# opg_receiver_schematics.net
KiCad netlist of a schematic drawn in Altium Designer
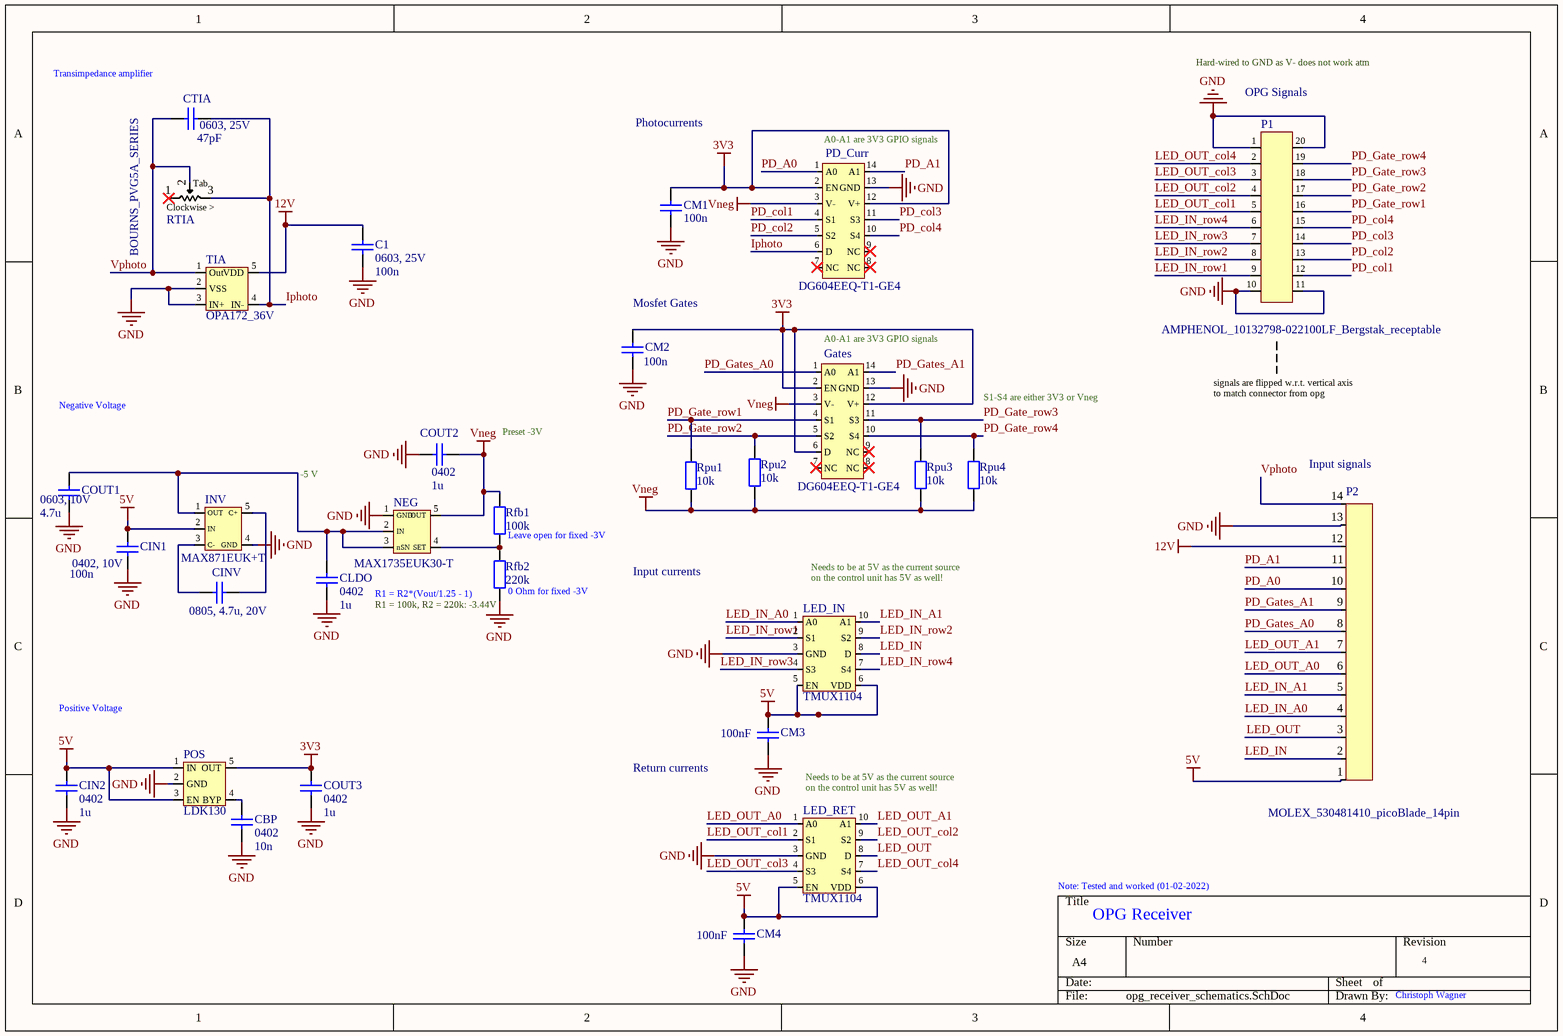
[diagram p0: opg_receiver_schematics.SchDoc]

(export (version "E")
  (design (tool "Eeschema 10.0.6"))
  (components
    (comp (ref "C1")
      (value "0603, 25V")
      (footprint "1608[0603]")
      (description "Capacitor (Semiconductor SIM Model)")
      (fields (field (name "ALTIUM_VALUE") "100n") (field (name "PUBLISHER") "Altium Limited"))
      (libsource (lib "Miscellaneous Devices") (part "Cap Semi"))
    )
    (comp (ref "CBP")
      (value "0402")
      (footprint "0402")
      (description "Capacitor (Semiconductor SIM Model)")
      (fields (field (name "ALTIUM_VALUE") "10n") (field (name "PUBLISHER") "Altium Limited"))
      (libsource (lib "Miscellaneous Devices") (part "Cap Semi"))
    )
    (comp (ref "CIN1")
      (value "0402, 10V")
      (footprint "1608[0603]")
      (description "Capacitor (Semiconductor SIM Model)")
      (fields (field (name "ALTIUM_VALUE") "100n") (field (name "PUBLISHER") "Altium Limited"))
      (libsource (lib "Miscellaneous Devices") (part "Cap Semi"))
    )
    (comp (ref "CIN2")
      (value "0402")
      (footprint "0402")
      (description "Capacitor (Semiconductor SIM Model)")
      (fields (field (name "ALTIUM_VALUE") "1u") (field (name "PUBLISHER") "Altium Limited"))
      (libsource (lib "Miscellaneous Devices") (part "Cap Semi"))
    )
    (comp (ref "CINV")
      (value "0805, 4.7u, 20V")
      (footprint "WCAP-CSGP_0805_H=0.8mm_Reflow")
      (description "WCAP-CSGP Multilayer Ceramic Chip Capacitor, General Purpose, size 0805, X7R, 680pF, 16V")
      (fields
        (field (name "MANUFACTURER PART NUMBER") "885012207032")
        (field (name "MANUFACTURER") "Wurth Elektronik")
      )
      (libsource (lib "capacitor_0805") (part "885012207032"))
    )
    (comp (ref "CLDO")
      (value "0402")
      (footprint "0402")
      (description "Capacitor (Semiconductor SIM Model)")
      (fields (field (name "ALTIUM_VALUE") "1u") (field (name "PUBLISHER") "Altium Limited"))
      (libsource (lib "Miscellaneous Devices") (part "Cap Semi"))
    )
    (comp (ref "CM1")
      (value "100n")
      (footprint "0402")
      (description "Capacitor (Semiconductor SIM Model)")
      (fields (field (name "PUBLISHER") "Altium Limited"))
      (libsource (lib "Miscellaneous Devices") (part "Cap Semi"))
    )
    (comp (ref "CM2")
      (value "100n")
      (footprint "0402")
      (description "Capacitor (Semiconductor SIM Model)")
      (fields (field (name "PUBLISHER") "Altium Limited"))
      (libsource (lib "Miscellaneous Devices") (part "Cap Semi"))
    )
    (comp (ref "CM3")
      (value "100nF")
      (footprint "0402")
      (description "Capacitor (Semiconductor SIM Model)")
      (fields (field (name "PUBLISHER") "Altium Limited"))
      (libsource (lib "Miscellaneous Devices") (part "Cap Semi"))
    )
    (comp (ref "CM4")
      (value "100nF")
      (footprint "0402")
      (description "Capacitor (Semiconductor SIM Model)")
      (fields (field (name "PUBLISHER") "Altium Limited"))
      (libsource (lib "Miscellaneous Devices") (part "Cap Semi"))
    )
    (comp (ref "COUT1")
      (value "0603, 10V")
      (footprint "1608[0603]")
      (description "Capacitor (Semiconductor SIM Model)")
      (fields (field (name "ALTIUM_VALUE") "4.7u") (field (name "PUBLISHER") "Altium Limited"))
      (libsource (lib "Miscellaneous Devices") (part "Cap Semi"))
    )
    (comp (ref "COUT2")
      (value "0402")
      (footprint "0402")
      (description "Capacitor (Semiconductor SIM Model)")
      (fields (field (name "ALTIUM_VALUE") "1u") (field (name "PUBLISHER") "Altium Limited"))
      (libsource (lib "Miscellaneous Devices") (part "Cap Semi"))
    )
    (comp (ref "COUT3")
      (value "0402")
      (footprint "0402")
      (description "Capacitor (Semiconductor SIM Model)")
      (fields (field (name "ALTIUM_VALUE") "1u") (field (name "PUBLISHER") "Altium Limited"))
      (libsource (lib "Miscellaneous Devices") (part "Cap Semi"))
    )
    (comp (ref "CTIA")
      (value "0603, 25V")
      (footprint "1608[0603]")
      (description "Capacitor (Semiconductor SIM Model)")
      (fields (field (name "ALTIUM_VALUE") "47pF") (field (name "PUBLISHER") "Altium Limited"))
      (libsource (lib "Miscellaneous Devices") (part "Cap Semi"))
    )
    (comp (ref "Gates")
      (value "DG604EEQ-T1-GE4")
      (footprint "DG604EEQ-T1-GE4")
      (description "Multiplex-Schalter IC CMOS 4:1 Multiplxr 14-pin TSSOP")
      (libsource (lib "Multiplexer") (part "DG604EEQ-T1-GE4"))
    )
    (comp (ref "INV")
      (value "MAX871EUK+T")
      (footprint "MAX871EUK+T")
      (description "500 kHz Switched-Capacitor Voltage Inverters")
      (libsource (lib "Regulator") (part "MAX871EUK+T"))
    )
    (comp (ref "LED_IN")
      (value "TMUX1104")
      (footprint "TMUX1104_legged")
      (description "4:1 MUX")
      (libsource (lib "Multiplexer") (part "TMUX1104"))
    )
    (comp (ref "LED_RET")
      (value "TMUX1104")
      (footprint "TMUX1104_legged")
      (description "4:1 MUX")
      (libsource (lib "Multiplexer") (part "TMUX1104"))
    )
    (comp (ref "NEG")
      (value "MAX1735EUK30-T")
      (footprint "MAX1735EUKxx-T")
      (libsource (lib "Regulator") (part "MAX1735EUKxx-T"))
    )
    (comp (ref "P1")
      (value "AMPHENOL_10132798-022100LF_Bergstak_receptable")
      (footprint "AMPHENOL_10132798-022100LF_Bergstak_receptable")
      (description "20 pin, 0.5 mm pitch, 3 mm mated height, female/receptable")
      (libsource (lib "Connectors") (part "AMPHENOL_10132798-022100LF_Bergstak_receptable"))
    )
    (comp (ref "P2")
      (value "MOLEX_530481410_picoBlade_14pin")
      (footprint "MOLEX_530481410_picoBlade_14pin")
      (libsource (lib "Connectors") (part "MOLEX_530481410_picoBlade_14pin"))
    )
    (comp (ref "PD_Curr")
      (value "DG604EEQ-T1-GE4")
      (footprint "DG604EEQ-T1-GE4")
      (description "Multiplex-Schalter IC CMOS 4:1 Multiplxr 14-pin TSSOP")
      (libsource (lib "Multiplexer") (part "DG604EEQ-T1-GE4"))
    )
    (comp (ref "POS")
      (value "LDK130")
      (footprint "LDK130")
      (description "300 mA low quiescent current very low noise LDO")
      (libsource (lib "Regulator") (part "LDK130"))
    )
    (comp (ref "Rfb1")
      (value "100k")
      (footprint "WRIS-KSKE_0805")
      (description "WRIS-KSKE SMT Thick Film Resistor, size 0805, 1Ohm, 0.33W")
      (fields
        (field (name "MANUFACTURER") "Wurth Elektronik")
        (field (name "MANUFACTURER PART NUMBER") "560050320011")
      )
      (libsource (lib "Wurth_thick_film_resistors") (part "560050320011"))
    )
    (comp (ref "Rfb2")
      (value "220k")
      (footprint "WRIS-KSKE_0805")
      (description "WRIS-KSKE SMT Thick Film Resistor, size 0805, 1Ohm, 0.33W")
      (fields
        (field (name "MANUFACTURER") "Wurth Elektronik")
        (field (name "MANUFACTURER PART NUMBER") "560050320011")
      )
      (libsource (lib "Wurth_thick_film_resistors") (part "560050320011"))
    )
    (comp (ref "Rpu1")
      (value "10k")
      (footprint "WRIS-KSKE_0402")
      (description "WRIS-KSKE SMT Thick Film Resistor, size 0402, 10Ohm, 0.125W")
      (fields
        (field (name "MANUFACTURER") "Wurth Elektronik")
        (field (name "MANUFACTURER PART NUMBER") "560050310009")
      )
      (libsource (lib "Wurth_thick_film_resistors") (part "560050310009"))
    )
    (comp (ref "Rpu2")
      (value "10k")
      (footprint "WRIS-KSKE_0402")
      (description "WRIS-KSKE SMT Thick Film Resistor, size 0402, 10Ohm, 0.125W")
      (fields
        (field (name "MANUFACTURER") "Wurth Elektronik")
        (field (name "MANUFACTURER PART NUMBER") "560050310009")
      )
      (libsource (lib "Wurth_thick_film_resistors") (part "560050310009"))
    )
    (comp (ref "Rpu3")
      (value "10k")
      (footprint "WRIS-KSKE_0402")
      (description "WRIS-KSKE SMT Thick Film Resistor, size 0402, 10Ohm, 0.125W")
      (fields
        (field (name "MANUFACTURER") "Wurth Elektronik")
        (field (name "MANUFACTURER PART NUMBER") "560050310009")
      )
      (libsource (lib "Wurth_thick_film_resistors") (part "560050310009"))
    )
    (comp (ref "Rpu4")
      (value "10k")
      (footprint "WRIS-KSKE_0402")
      (description "WRIS-KSKE SMT Thick Film Resistor, size 0402, 10Ohm, 0.125W")
      (fields
        (field (name "MANUFACTURER") "Wurth Elektronik")
        (field (name "MANUFACTURER PART NUMBER") "560050310009")
      )
      (libsource (lib "Wurth_thick_film_resistors") (part "560050310009"))
    )
    (comp (ref "RTIA")
      (value "BOURNS_PVG5A_SERIES")
      (footprint "BOURNS_PVG5A_SERIES")
      (libsource (lib "Potentiometer") (part "BOURNS_PVG5A_SERIES"))
    )
    (comp (ref "TIA")
      (value "OPA172_36V")
      (footprint "OPA172_36V_SC70-5")
      (description "OPAx172 36-V, Single-Supply, 10-MHz, Rail-to-Rail Output Operational Amplifiers")
      (libsource (lib "OP_Amps") (part "OPA172_36V"))
    )
  )
  (nets
    (net (code "1") (name "/Iphoto") (class "Default")
      (node (ref "CTIA") (pin "1") (pinfunction "1_1") (pintype "passive"))
      (node (ref "PD_Curr") (pin "6") (pinfunction "D_6") (pintype "passive"))
      (node (ref "RTIA") (pin "3") (pintype "passive"))
      (node (ref "TIA") (pin "4") (pinfunction "IN-_4") (pintype "passive"))
    )
    (net (code "2") (name "/LED_IN") (class "Default")
      (node (ref "LED_IN") (pin "8") (pinfunction "D_8") (pintype "passive"))
      (node (ref "P2") (pin "2") (pintype "passive"))
    )
    (net (code "3") (name "/LED_IN_A0") (class "Default")
      (node (ref "LED_IN") (pin "1") (pinfunction "A0_1") (pintype "passive"))
      (node (ref "P2") (pin "4") (pintype "passive"))
    )
    (net (code "4") (name "/LED_IN_A1") (class "Default")
      (node (ref "LED_IN") (pin "10") (pinfunction "A1_10") (pintype "passive"))
      (node (ref "P2") (pin "5") (pintype "passive"))
    )
    (net (code "5") (name "/LED_IN_row1") (class "Default")
      (node (ref "LED_IN") (pin "2") (pinfunction "S1_2") (pintype "passive"))
      (node (ref "P1") (pin "9") (pintype "passive"))
    )
    (net (code "6") (name "/LED_IN_row2") (class "Default")
      (node (ref "LED_IN") (pin "9") (pinfunction "S2_9") (pintype "passive"))
      (node (ref "P1") (pin "8") (pintype "passive"))
    )
    (net (code "7") (name "/LED_IN_row3") (class "Default")
      (node (ref "LED_IN") (pin "4") (pinfunction "S3_4") (pintype "passive"))
      (node (ref "P1") (pin "7") (pintype "passive"))
    )
    (net (code "8") (name "/LED_IN_row4") (class "Default")
      (node (ref "LED_IN") (pin "7") (pinfunction "S4_7") (pintype "passive"))
      (node (ref "P1") (pin "6") (pintype "passive"))
    )
    (net (code "9") (name "/LED_OUT") (class "Default")
      (node (ref "LED_RET") (pin "8") (pinfunction "D_8") (pintype "passive"))
      (node (ref "P2") (pin "3") (pintype "passive"))
    )
    (net (code "10") (name "/LED_OUT_A0") (class "Default")
      (node (ref "LED_RET") (pin "1") (pinfunction "A0_1") (pintype "passive"))
      (node (ref "P2") (pin "6") (pintype "passive"))
    )
    (net (code "11") (name "/LED_OUT_A1") (class "Default")
      (node (ref "LED_RET") (pin "10") (pinfunction "A1_10") (pintype "passive"))
      (node (ref "P2") (pin "7") (pintype "passive"))
    )
    (net (code "12") (name "/LED_OUT_col1") (class "Default")
      (node (ref "LED_RET") (pin "2") (pinfunction "S1_2") (pintype "passive"))
      (node (ref "P1") (pin "5") (pintype "passive"))
    )
    (net (code "13") (name "/LED_OUT_col2") (class "Default")
      (node (ref "LED_RET") (pin "9") (pinfunction "S2_9") (pintype "passive"))
      (node (ref "P1") (pin "4") (pintype "passive"))
    )
    (net (code "14") (name "/LED_OUT_col3") (class "Default")
      (node (ref "LED_RET") (pin "4") (pinfunction "S3_4") (pintype "passive"))
      (node (ref "P1") (pin "3") (pintype "passive"))
    )
    (net (code "15") (name "/LED_OUT_col4") (class "Default")
      (node (ref "LED_RET") (pin "7") (pinfunction "S4_7") (pintype "passive"))
      (node (ref "P1") (pin "2") (pintype "passive"))
    )
    (net (code "16") (name "/PD_A0") (class "Default")
      (node (ref "P2") (pin "10") (pintype "passive"))
      (node (ref "PD_Curr") (pin "1") (pinfunction "A0_1") (pintype "passive"))
    )
    (net (code "17") (name "/PD_A1") (class "Default")
      (node (ref "P2") (pin "11") (pintype "passive"))
      (node (ref "PD_Curr") (pin "14") (pinfunction "A1_14") (pintype "passive"))
    )
    (net (code "18") (name "/PD_Gate_row1") (class "Default")
      (node (ref "Gates") (pin "4") (pinfunction "S1_4") (pintype "passive"))
      (node (ref "P1") (pin "16") (pintype "passive"))
      (node (ref "Rpu1") (pin "2") (pinfunction "2_2") (pintype "passive"))
    )
    (net (code "19") (name "/PD_Gate_row2") (class "Default")
      (node (ref "Gates") (pin "5") (pinfunction "S2_5") (pintype "passive"))
      (node (ref "P1") (pin "17") (pintype "passive"))
      (node (ref "Rpu2") (pin "2") (pinfunction "2_2") (pintype "passive"))
    )
    (net (code "20") (name "/PD_Gate_row3") (class "Default")
      (node (ref "Gates") (pin "11") (pinfunction "S3_11") (pintype "passive"))
      (node (ref "P1") (pin "18") (pintype "passive"))
      (node (ref "Rpu3") (pin "2") (pinfunction "2_2") (pintype "passive"))
    )
    (net (code "21") (name "/PD_Gate_row4") (class "Default")
      (node (ref "Gates") (pin "10") (pinfunction "S4_10") (pintype "passive"))
      (node (ref "P1") (pin "19") (pintype "passive"))
      (node (ref "Rpu4") (pin "2") (pinfunction "2_2") (pintype "passive"))
    )
    (net (code "22") (name "/PD_Gates_A0") (class "Default")
      (node (ref "Gates") (pin "1") (pinfunction "A0_1") (pintype "passive"))
      (node (ref "P2") (pin "8") (pintype "passive"))
    )
    (net (code "23") (name "/PD_Gates_A1") (class "Default")
      (node (ref "Gates") (pin "14") (pinfunction "A1_14") (pintype "passive"))
      (node (ref "P2") (pin "9") (pintype "passive"))
    )
    (net (code "24") (name "/PD_col1") (class "Default")
      (node (ref "P1") (pin "12") (pintype "passive"))
      (node (ref "PD_Curr") (pin "4") (pinfunction "S1_4") (pintype "passive"))
    )
    (net (code "25") (name "/PD_col2") (class "Default")
      (node (ref "P1") (pin "13") (pintype "passive"))
      (node (ref "PD_Curr") (pin "5") (pinfunction "S2_5") (pintype "passive"))
    )
    (net (code "26") (name "/PD_col3") (class "Default")
      (node (ref "P1") (pin "14") (pintype "passive"))
      (node (ref "PD_Curr") (pin "11") (pinfunction "S3_11") (pintype "passive"))
    )
    (net (code "27") (name "/PD_col4") (class "Default")
      (node (ref "P1") (pin "15") (pintype "passive"))
      (node (ref "PD_Curr") (pin "10") (pinfunction "S4_10") (pintype "passive"))
    )
    (net (code "28") (name "/Vphoto") (class "Default")
      (node (ref "CTIA") (pin "2") (pinfunction "2_2") (pintype "passive"))
      (node (ref "P2") (pin "14") (pintype "passive"))
      (node (ref "RTIA") (pin "2") (pintype "passive"))
      (node (ref "TIA") (pin "1") (pinfunction "Out_1") (pintype "passive"))
    )
    (net (code "29") (name "3V3") (class "Default")
      (node (ref "CM1") (pin "2") (pinfunction "2_2") (pintype "passive"))
      (node (ref "CM2") (pin "2") (pinfunction "2_2") (pintype "passive"))
      (node (ref "COUT3") (pin "2") (pinfunction "2_2") (pintype "passive"))
      (node (ref "Gates") (pin "12") (pinfunction "V+_12") (pintype "passive"))
      (node (ref "Gates") (pin "2") (pinfunction "EN_2") (pintype "passive"))
      (node (ref "Gates") (pin "6") (pinfunction "D_6") (pintype "passive"))
      (node (ref "PD_Curr") (pin "12") (pinfunction "V+_12") (pintype "passive"))
      (node (ref "PD_Curr") (pin "2") (pinfunction "EN_2") (pintype "passive"))
      (node (ref "POS") (pin "5") (pinfunction "OUT_5") (pintype "passive"))
    )
    (net (code "30") (name "5V") (class "Default")
      (node (ref "CIN1") (pin "2") (pinfunction "2_2") (pintype "passive"))
      (node (ref "CIN2") (pin "1") (pinfunction "1_1") (pintype "passive"))
      (node (ref "CM3") (pin "1") (pinfunction "1_1") (pintype "passive"))
      (node (ref "CM4") (pin "2") (pinfunction "2_2") (pintype "passive"))
      (node (ref "INV") (pin "2") (pinfunction "IN_2") (pintype "passive"))
      (node (ref "LED_IN") (pin "5") (pinfunction "EN_5") (pintype "passive"))
      (node (ref "LED_IN") (pin "6") (pinfunction "VDD_6") (pintype "passive"))
      (node (ref "LED_RET") (pin "5") (pinfunction "EN_5") (pintype "passive"))
      (node (ref "LED_RET") (pin "6") (pinfunction "VDD_6") (pintype "passive"))
      (node (ref "P2") (pin "1") (pintype "passive"))
      (node (ref "POS") (pin "1") (pinfunction "IN_1") (pintype "passive"))
      (node (ref "POS") (pin "3") (pinfunction "EN_3") (pintype "passive"))
    )
    (net (code "31") (name "12V") (class "Default")
      (node (ref "C1") (pin "2") (pinfunction "2_2") (pintype "passive"))
      (node (ref "P2") (pin "12") (pintype "passive"))
      (node (ref "TIA") (pin "5") (pinfunction "VDD_5") (pintype "passive"))
    )
    (net (code "32") (name "GND") (class "Default")
      (node (ref "C1") (pin "1") (pinfunction "1_1") (pintype "passive"))
      (node (ref "CBP") (pin "2") (pinfunction "2_2") (pintype "passive"))
      (node (ref "CIN1") (pin "1") (pinfunction "1_1") (pintype "passive"))
      (node (ref "CIN2") (pin "2") (pinfunction "2_2") (pintype "passive"))
      (node (ref "CLDO") (pin "2") (pinfunction "2_2") (pintype "passive"))
      (node (ref "CM1") (pin "1") (pinfunction "1_1") (pintype "passive"))
      (node (ref "CM2") (pin "1") (pinfunction "1_1") (pintype "passive"))
      (node (ref "CM3") (pin "2") (pinfunction "2_2") (pintype "passive"))
      (node (ref "CM4") (pin "1") (pinfunction "1_1") (pintype "passive"))
      (node (ref "COUT1") (pin "2") (pinfunction "2_2") (pintype "passive"))
      (node (ref "COUT2") (pin "1") (pinfunction "1_1") (pintype "passive"))
      (node (ref "COUT3") (pin "1") (pinfunction "1_1") (pintype "passive"))
      (node (ref "Gates") (pin "13") (pinfunction "GND_13") (pintype "passive"))
      (node (ref "INV") (pin "4") (pinfunction "GND_4") (pintype "passive"))
      (node (ref "LED_IN") (pin "3") (pinfunction "GND_3") (pintype "passive"))
      (node (ref "LED_RET") (pin "3") (pinfunction "GND_3") (pintype "passive"))
      (node (ref "NEG") (pin "1") (pinfunction "GND_1") (pintype "passive"))
      (node (ref "P1") (pin "1") (pintype "passive"))
      (node (ref "P1") (pin "10") (pintype "passive"))
      (node (ref "P1") (pin "11") (pintype "passive"))
      (node (ref "P1") (pin "20") (pintype "passive"))
      (node (ref "P2") (pin "13") (pintype "passive"))
      (node (ref "PD_Curr") (pin "13") (pinfunction "GND_13") (pintype "passive"))
      (node (ref "POS") (pin "2") (pinfunction "GND_2") (pintype "passive"))
      (node (ref "Rfb2") (pin "2") (pinfunction "2_2") (pintype "passive"))
      (node (ref "TIA") (pin "2") (pinfunction "VSS_2") (pintype "passive"))
      (node (ref "TIA") (pin "3") (pinfunction "IN+_3") (pintype "passive"))
    )
    (net (code "33") (name "Net-(INV-C+)") (class "Default")
      (node (ref "CINV") (pin "2") (pinfunction "2_2") (pintype "passive"))
      (node (ref "INV") (pin "5") (pinfunction "C+_5") (pintype "passive"))
    )
    (net (code "34") (name "Net-(INV-C-)") (class "Default")
      (node (ref "CINV") (pin "1") (pinfunction "1_1") (pintype "passive"))
      (node (ref "INV") (pin "3") (pinfunction "C-_3") (pintype "passive"))
    )
    (net (code "35") (name "Net-(INV-OUT)") (class "Default")
      (node (ref "CLDO") (pin "1") (pinfunction "1_1") (pintype "passive"))
      (node (ref "COUT1") (pin "1") (pinfunction "1_1") (pintype "passive"))
      (node (ref "INV") (pin "1") (pinfunction "OUT_1") (pintype "passive"))
      (node (ref "NEG") (pin "2") (pinfunction "IN_2") (pintype "passive"))
      (node (ref "NEG") (pin "3") (pinfunction "nSN_3") (pintype "passive"))
    )
    (net (code "36") (name "Net-(NEG-SET)") (class "Default")
      (node (ref "NEG") (pin "4") (pinfunction "SET_4") (pintype "passive"))
      (node (ref "Rfb1") (pin "2") (pinfunction "2_2") (pintype "passive"))
      (node (ref "Rfb2") (pin "1") (pinfunction "1_1") (pintype "passive"))
    )
    (net (code "37") (name "Net-(POS-BYP)") (class "Default")
      (node (ref "CBP") (pin "1") (pinfunction "1_1") (pintype "passive"))
      (node (ref "POS") (pin "4") (pinfunction "BYP_4") (pintype "passive"))
    )
    (net (code "38") (name "Vneg") (class "Default")
      (node (ref "COUT2") (pin "2") (pinfunction "2_2") (pintype "passive"))
      (node (ref "Gates") (pin "3") (pinfunction "V-_3") (pintype "passive"))
      (node (ref "NEG") (pin "5") (pinfunction "OUT_5") (pintype "passive"))
      (node (ref "PD_Curr") (pin "3") (pinfunction "V-_3") (pintype "passive"))
      (node (ref "Rfb1") (pin "1") (pinfunction "1_1") (pintype "passive"))
      (node (ref "Rpu1") (pin "1") (pinfunction "1_1") (pintype "passive"))
      (node (ref "Rpu2") (pin "1") (pinfunction "1_1") (pintype "passive"))
      (node (ref "Rpu3") (pin "1") (pinfunction "1_1") (pintype "passive"))
      (node (ref "Rpu4") (pin "1") (pinfunction "1_1") (pintype "passive"))
    )
    (net (code "39") (name "unconnected-(Gates-NC-Pad7)") (class "Default")
      (node (ref "Gates") (pin "7") (pinfunction "NC_7") (pintype "passive+no_connect"))
    )
    (net (code "40") (name "unconnected-(Gates-NC-Pad8)") (class "Default")
      (node (ref "Gates") (pin "8") (pinfunction "NC_8") (pintype "passive+no_connect"))
    )
    (net (code "41") (name "unconnected-(Gates-NC-Pad9)") (class "Default")
      (node (ref "Gates") (pin "9") (pinfunction "NC_9") (pintype "passive+no_connect"))
    )
    (net (code "42") (name "unconnected-(PD_Curr-NC-Pad7)") (class "Default")
      (node (ref "PD_Curr") (pin "7") (pinfunction "NC_7") (pintype "passive+no_connect"))
    )
    (net (code "43") (name "unconnected-(PD_Curr-NC-Pad8)") (class "Default")
      (node (ref "PD_Curr") (pin "8") (pinfunction "NC_8") (pintype "passive+no_connect"))
    )
    (net (code "44") (name "unconnected-(PD_Curr-NC-Pad9)") (class "Default")
      (node (ref "PD_Curr") (pin "9") (pinfunction "NC_9") (pintype "passive+no_connect"))
    )
    (net (code "45") (name "unconnected-(RTIA-Pad1)") (class "Default")
      (node (ref "RTIA") (pin "1") (pintype "passive+no_connect"))
    )
  )
)
